# SRF05.net
KiCad netlist of a schematic drawn in Altium Designer
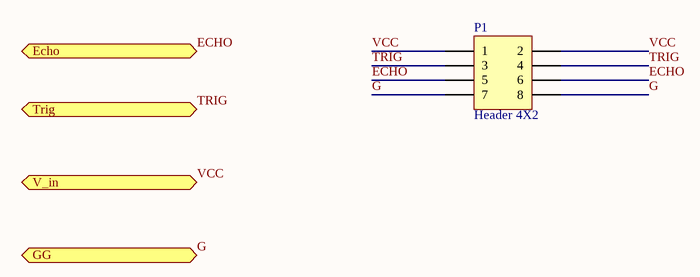
[diagram p0: SRF05.SchDoc]

(export (version "E")
  (design (tool "Eeschema 10.0.6"))
  (components
    (comp (ref "P1")
      (value "Header 4X2")
      (footprint "HDR2X4")
      (description "Header, 4-Pin, Dual row")
      (fields (field (name "PUBLISHER") "Altium Limited"))
      (libsource (lib "Miscellaneous Connectors") (part "Header 4X2"))
    )
  )
  (nets
    (net (code "1") (name "/ECHO") (class "Default")
      (node (ref "P1") (pin "5") (pinfunction "5_5") (pintype "passive"))
      (node (ref "P1") (pin "6") (pinfunction "6_6") (pintype "passive"))
    )
    (net (code "2") (name "/G") (class "Default")
      (node (ref "P1") (pin "7") (pinfunction "7_7") (pintype "passive"))
      (node (ref "P1") (pin "8") (pinfunction "8_8") (pintype "passive"))
    )
    (net (code "3") (name "/TRIG") (class "Default")
      (node (ref "P1") (pin "3") (pinfunction "3_3") (pintype "passive"))
      (node (ref "P1") (pin "4") (pinfunction "4_4") (pintype "passive"))
    )
    (net (code "4") (name "/VCC") (class "Default")
      (node (ref "P1") (pin "1") (pinfunction "1_1") (pintype "passive"))
      (node (ref "P1") (pin "2") (pinfunction "2_2") (pintype "passive"))
    )
  )
)
